# schematic.net
KiCad netlist of a schematic drawn in EAGLE
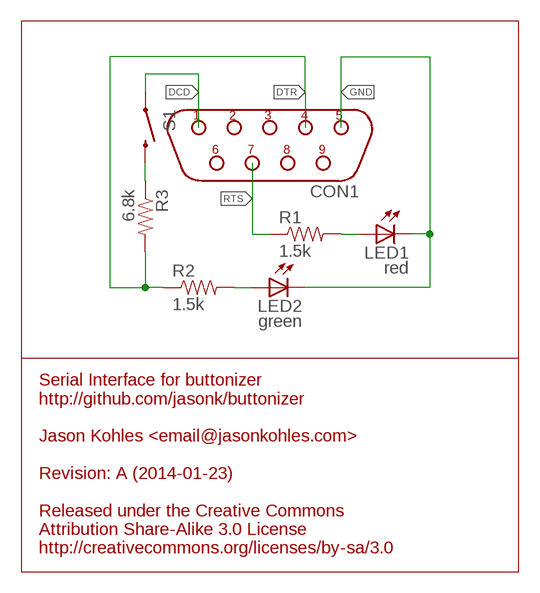
[diagram p0: schematic, sheet 1]

(export (version "E")
  (design (tool "Eeschema 10.0.6"))
  (components
    (comp (ref "CON1")
      (value "DB9F")
      (footprint "eagle-import:D-09F")
      (libsource (lib "eagle-import") (part "DB9F"))
    )
    (comp (ref "LED1")
      (value "red")
      (footprint "eagle-import:LED5MM")
      (libsource (lib "eagle-import") (part "LED5MM"))
    )
    (comp (ref "LED2")
      (value "green")
      (footprint "eagle-import:LED5MM")
      (libsource (lib "eagle-import") (part "LED5MM"))
    )
    (comp (ref "R1")
      (value "1.5k")
      (footprint "eagle-import:AXIAL-0.5")
      (libsource (lib "eagle-import") (part "RESISTORPTH-1/2W"))
    )
    (comp (ref "R2")
      (value "1.5k")
      (footprint "eagle-import:AXIAL-0.5")
      (libsource (lib "eagle-import") (part "RESISTORPTH-1/2W"))
    )
    (comp (ref "R3")
      (value "6.8k")
      (footprint "eagle-import:AXIAL-0.5")
      (libsource (lib "eagle-import") (part "RESISTORPTH-1/2W"))
    )
    (comp (ref "S1")
      (value "SWITCH-MOMENTARY-212MM")
      (footprint "eagle-import:TACTILE-PTH-12MM")
      (libsource (lib "eagle-import") (part "SWITCH-MOMENTARY-212MM"))
    )
  )
  (nets
    (net (code "1") (name "DCD") (class "Default")
      (node (ref "CON1") (pin "1") (pinfunction "1_1") (pintype "passive"))
      (node (ref "S1") (pin "1") (pinfunction "1_1") (pintype "passive"))
    )
    (net (code "2") (name "DTR") (class "Default")
      (node (ref "CON1") (pin "4") (pinfunction "4_4") (pintype "passive"))
      (node (ref "R2") (pin "P$1") (pinfunction "1_P$1") (pintype "passive"))
      (node (ref "R3") (pin "P$2") (pinfunction "2_P$2") (pintype "passive"))
    )
    (net (code "3") (name "GND") (class "Default")
      (node (ref "CON1") (pin "5") (pinfunction "5_5") (pintype "passive"))
      (node (ref "LED1") (pin "K") (pinfunction "C_K") (pintype "passive"))
      (node (ref "LED2") (pin "K") (pinfunction "C_K") (pintype "passive"))
    )
    (net (code "4") (name "Net-(R1-2)") (class "Default")
      (node (ref "LED1") (pin "A") (pinfunction "A_A") (pintype "passive"))
      (node (ref "R1") (pin "P$2") (pinfunction "2_P$2") (pintype "passive"))
    )
    (net (code "5") (name "Net-(R2-2)") (class "Default")
      (node (ref "LED2") (pin "A") (pinfunction "A_A") (pintype "passive"))
      (node (ref "R2") (pin "P$2") (pinfunction "2_P$2") (pintype "passive"))
    )
    (net (code "6") (name "Net-(R3-1)") (class "Default")
      (node (ref "R3") (pin "P$1") (pinfunction "1_P$1") (pintype "passive"))
      (node (ref "S1") (pin "3") (pinfunction "2_3") (pintype "passive"))
    )
    (net (code "7") (name "RTS") (class "Default")
      (node (ref "CON1") (pin "7") (pinfunction "7_7") (pintype "passive"))
      (node (ref "R1") (pin "P$1") (pinfunction "1_P$1") (pintype "passive"))
    )
    (net (code "8") (name "unconnected-(CON1-Pad2)") (class "Default")
      (node (ref "CON1") (pin "2") (pinfunction "2_2") (pintype "passive"))
    )
    (net (code "9") (name "unconnected-(CON1-Pad3)") (class "Default")
      (node (ref "CON1") (pin "3") (pinfunction "3_3") (pintype "passive"))
    )
    (net (code "10") (name "unconnected-(CON1-Pad6)") (class "Default")
      (node (ref "CON1") (pin "6") (pinfunction "6_6") (pintype "passive"))
    )
    (net (code "11") (name "unconnected-(CON1-Pad8)") (class "Default")
      (node (ref "CON1") (pin "8") (pinfunction "8_8") (pintype "passive"))
    )
    (net (code "12") (name "unconnected-(CON1-Pad9)") (class "Default")
      (node (ref "CON1") (pin "9") (pinfunction "9_9") (pintype "passive"))
    )
  )
)
